# 3_MCU.net
KiCad netlist of a schematic drawn in Altium Designer
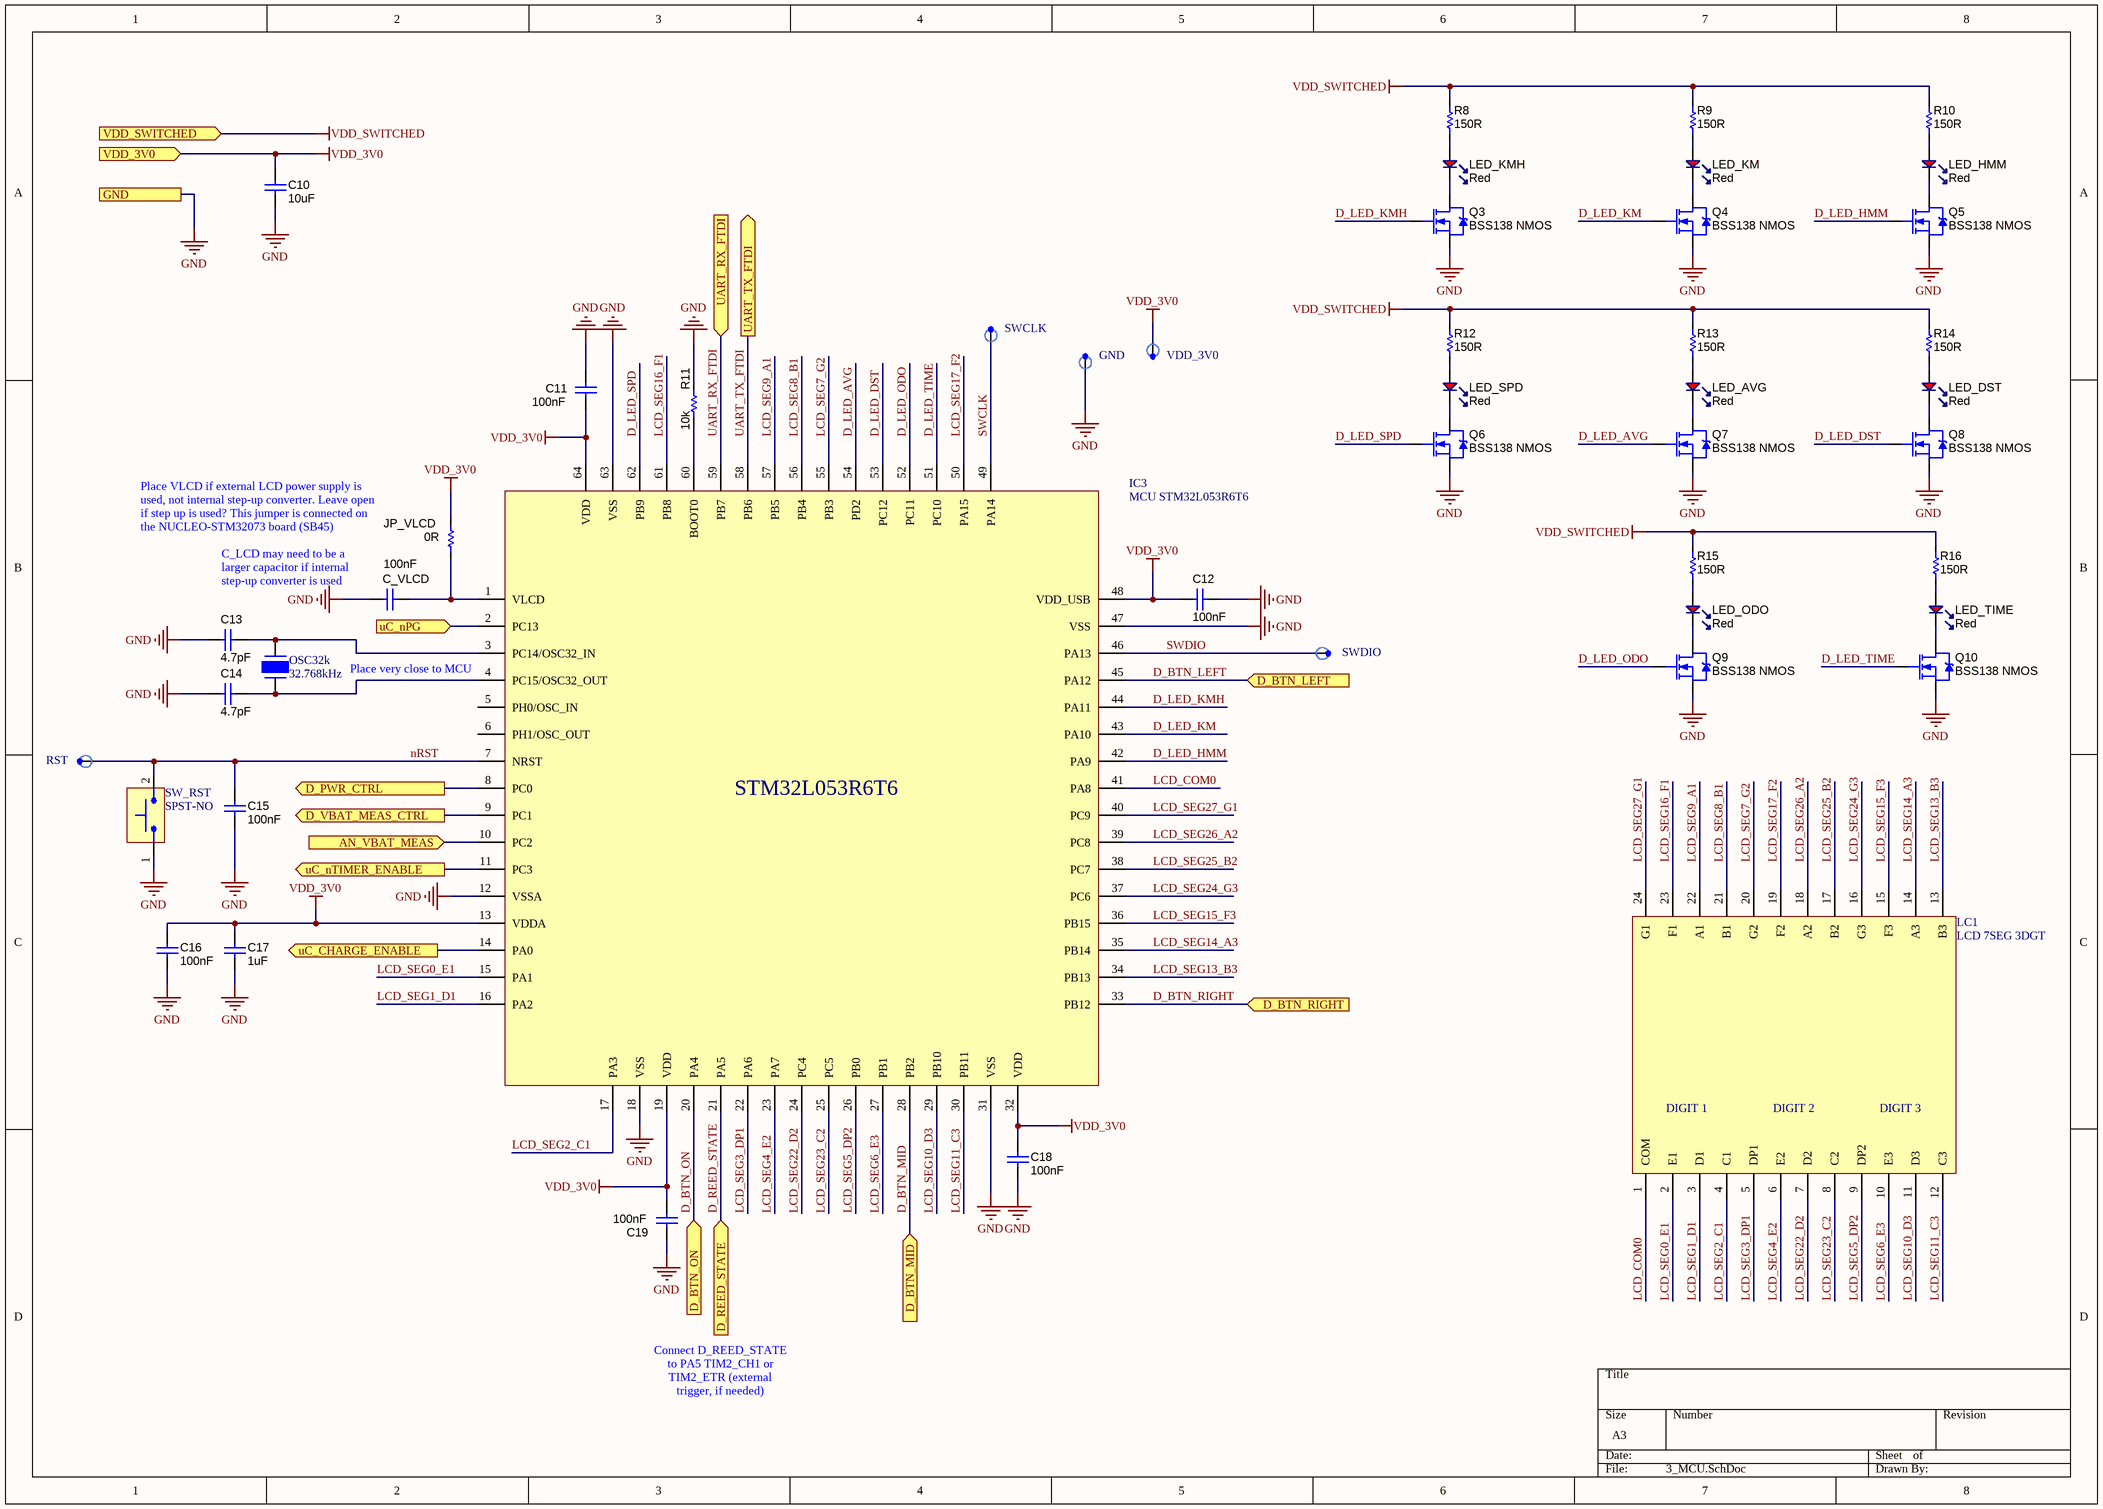
[diagram p0: 3_MCU.SchDoc]

(export (version "E")
  (design (tool "Eeschema 10.0.6"))
  (components
    (comp (ref "C10")
      (value "10uF")
      (footprint "CAP_0603")
      (description "Cermacic Capacitor 0603 16V 10uF")
      (fields (field (name "MANUFACTURER") "n/a"))
      (libsource (lib "Diplomski") (part "CAP_10uF_16V_0603"))
    )
    (comp (ref "C11")
      (value "100nF")
      (footprint "CAP_0603")
      (description "Cermacic Capacitor 0603 50V 100nF")
      (fields (field (name "MANUFACTURER") "n/a"))
      (libsource (lib "Diplomski") (part "CAP_100nF_50V_0603"))
    )
    (comp (ref "C12")
      (value "100nF")
      (footprint "CAP_0603")
      (description "Cermacic Capacitor 0603 50V 100nF")
      (fields (field (name "MANUFACTURER") "n/a"))
      (libsource (lib "Diplomski") (part "CAP_100nF_50V_0603"))
    )
    (comp (ref "C13")
      (value "4.7pF")
      (footprint "CAP_0603")
      (description "Ceramic Capacitor 0603 63V 4.7pF NPO")
      (fields (field (name "MANUFACTURER") "n/a"))
      (libsource (lib "Diplomski") (part "CAP_4.7pF_63V_NPO_0603"))
    )
    (comp (ref "C14")
      (value "4.7pF")
      (footprint "CAP_0603")
      (description "Ceramic Capacitor 0603 63V 4.7pF NPO")
      (fields (field (name "MANUFACTURER") "n/a"))
      (libsource (lib "Diplomski") (part "CAP_4.7pF_63V_NPO_0603"))
    )
    (comp (ref "C15")
      (value "100nF")
      (footprint "CAP_0603")
      (description "Cermacic Capacitor 0603 50V 100nF")
      (fields (field (name "MANUFACTURER") "n/a"))
      (libsource (lib "Diplomski") (part "CAP_100nF_50V_0603"))
    )
    (comp (ref "C16")
      (value "100nF")
      (footprint "CAP_0603")
      (description "Cermacic Capacitor 0603 50V 100nF")
      (fields (field (name "MANUFACTURER") "n/a"))
      (libsource (lib "Diplomski") (part "CAP_100nF_50V_0603"))
    )
    (comp (ref "C17")
      (value "1uF")
      (footprint "CAP_0603")
      (description "Cermacic Capacitor 0603 16V 1uF")
      (fields (field (name "MANUFACTURER") "n/a"))
      (libsource (lib "Diplomski") (part "CAP_1uF_16V_0603"))
    )
    (comp (ref "C18")
      (value "100nF")
      (footprint "CAP_0603")
      (description "Cermacic Capacitor 0603 50V 100nF")
      (fields (field (name "MANUFACTURER") "n/a"))
      (libsource (lib "Diplomski") (part "CAP_100nF_50V_0603"))
    )
    (comp (ref "C19")
      (value "100nF")
      (footprint "CAP_0603")
      (description "Cermacic Capacitor 0603 50V 100nF")
      (fields (field (name "MANUFACTURER") "n/a"))
      (libsource (lib "Diplomski") (part "CAP_100nF_50V_0603"))
    )
    (comp (ref "C_VLCD")
      (value "100nF")
      (footprint "CAP_0603")
      (description "Cermacic Capacitor 0603 50V 100nF")
      (fields (field (name "MANUFACTURER") "n/a"))
      (libsource (lib "Diplomski") (part "CAP_100nF_50V_0603"))
    )
    (comp (ref "GND")
      (value "Testpoint_SMD")
      (footprint "Testpoint_SMD")
      (libsource (lib "Diplomski") (part "Testpoint_SMD"))
    )
    (comp (ref "IC3")
      (value "MCU STM32L053R6T6")
      (footprint "LQFP-64")
      (description "IC MCU STM32L053R6T6 LQFP-64")
      (fields
        (field (name "MANUFACTURER") "STMicroelectronics")
        (field (name "MANUFACTURER PART NUMBER") "STM32L053R6T6")
      )
      (libsource (lib "Diplomski") (part "IC_MCU_STM32L053R6T6_64LQFP"))
    )
    (comp (ref "JP_VLCD")
      (value "0R")
      (footprint "RES_0603")
      (description "Resistor SMD 0603 0R 0.1W 1%")
      (fields (field (name "MANUFACTURER") "n/a") (field (name "TOLERANCE") "1%"))
      (libsource (lib "Diplomski") (part "RES_0R_1%_0.1W_0603"))
    )
    (comp (ref "LC1")
      (value "LCD 7SEG 3DGT")
      (footprint "24 pin 3 digit LCD (7.9mm character height)")
      (description "7 segment LCD display, 3 digits, 0.31in (7.9mm) character height. 3-5V")
      (fields
        (field (name "MANUFACTURER") "Lumex Opto/Components Inc.")
        (field (name "MANUFACTURER PART NUMBER") "LCD-S301C31TR")
      )
      (libsource (lib "Diplomski") (part "LCD_7SEG_3DIGIT_0.31in"))
    )
    (comp (ref "LED_AVG")
      (value "Red")
      (footprint "LED_0603")
      (description "LED Diode SMD Green")
      (fields (field (name "MANUFACTURER") "n/a"))
      (libsource (lib "Diplomski") (part "LED_Red_2V_20mA_0603"))
    )
    (comp (ref "LED_DST")
      (value "Red")
      (footprint "LED_0603")
      (description "LED Diode SMD Green")
      (fields (field (name "MANUFACTURER") "n/a"))
      (libsource (lib "Diplomski") (part "LED_Red_2V_20mA_0603"))
    )
    (comp (ref "LED_HMM")
      (value "Red")
      (footprint "LED_0603")
      (description "LED Diode SMD Green")
      (fields (field (name "MANUFACTURER") "n/a"))
      (libsource (lib "Diplomski") (part "LED_Red_2V_20mA_0603"))
    )
    (comp (ref "LED_KM")
      (value "Red")
      (footprint "LED_0603")
      (description "LED Diode SMD Green")
      (fields (field (name "MANUFACTURER") "n/a"))
      (libsource (lib "Diplomski") (part "LED_Red_2V_20mA_0603"))
    )
    (comp (ref "LED_KMH")
      (value "Red")
      (footprint "LED_0603")
      (description "LED Diode SMD Green")
      (fields (field (name "MANUFACTURER") "n/a"))
      (libsource (lib "Diplomski") (part "LED_Red_2V_20mA_0603"))
    )
    (comp (ref "LED_ODO")
      (value "Red")
      (footprint "LED_0603")
      (description "LED Diode SMD Green")
      (fields (field (name "MANUFACTURER") "n/a"))
      (libsource (lib "Diplomski") (part "LED_Red_2V_20mA_0603"))
    )
    (comp (ref "LED_SPD")
      (value "Red")
      (footprint "LED_0603")
      (description "LED Diode SMD Green")
      (fields (field (name "MANUFACTURER") "n/a"))
      (libsource (lib "Diplomski") (part "LED_Red_2V_20mA_0603"))
    )
    (comp (ref "LED_TIME")
      (value "Red")
      (footprint "LED_0603")
      (description "LED Diode SMD Green")
      (fields (field (name "MANUFACTURER") "n/a"))
      (libsource (lib "Diplomski") (part "LED_Red_2V_20mA_0603"))
    )
    (comp (ref "OSC32k")
      (value "32.768kHz")
      (footprint "2x6mm cylindrical can - 0.7mm through hole")
      (description "SMD Tactile switch 2 pin 6x3.5mm SPST-NO 5mm height")
      (fields (field (name "MANUFACTURER") "YIC") (field (name "MANUFACTURER PART NUMBER") "32.768K26/DT26"))
      (libsource (lib "Diplomski") (part "OSCILLATOR_CRYSTAL_32.768kHz_DT26"))
    )
    (comp (ref "Q3")
      (value "BSS138 NMOS")
      (footprint "SOT-23-3")
      (description "MOSFET N-channel SMD BSS138 220mA 50V")
      (fields (field (name "MANUFACTURER") "ONsemi") (field (name "MANUFACTURER PART NUMBER") "BSS138"))
      (libsource (lib "Diplomski") (part "MOSFET_N_60V_220mA_BSS138_SOT-23"))
    )
    (comp (ref "Q4")
      (value "BSS138 NMOS")
      (footprint "SOT-23-3")
      (description "MOSFET N-channel SMD BSS138 220mA 50V")
      (fields (field (name "MANUFACTURER") "ONsemi") (field (name "MANUFACTURER PART NUMBER") "BSS138"))
      (libsource (lib "Diplomski") (part "MOSFET_N_60V_220mA_BSS138_SOT-23"))
    )
    (comp (ref "Q5")
      (value "BSS138 NMOS")
      (footprint "SOT-23-3")
      (description "MOSFET N-channel SMD BSS138 220mA 50V")
      (fields (field (name "MANUFACTURER") "ONsemi") (field (name "MANUFACTURER PART NUMBER") "BSS138"))
      (libsource (lib "Diplomski") (part "MOSFET_N_60V_220mA_BSS138_SOT-23"))
    )
    (comp (ref "Q6")
      (value "BSS138 NMOS")
      (footprint "SOT-23-3")
      (description "MOSFET N-channel SMD BSS138 220mA 50V")
      (fields (field (name "MANUFACTURER") "ONsemi") (field (name "MANUFACTURER PART NUMBER") "BSS138"))
      (libsource (lib "Diplomski") (part "MOSFET_N_60V_220mA_BSS138_SOT-23"))
    )
    (comp (ref "Q7")
      (value "BSS138 NMOS")
      (footprint "SOT-23-3")
      (description "MOSFET N-channel SMD BSS138 220mA 50V")
      (fields (field (name "MANUFACTURER") "ONsemi") (field (name "MANUFACTURER PART NUMBER") "BSS138"))
      (libsource (lib "Diplomski") (part "MOSFET_N_60V_220mA_BSS138_SOT-23"))
    )
    (comp (ref "Q8")
      (value "BSS138 NMOS")
      (footprint "SOT-23-3")
      (description "MOSFET N-channel SMD BSS138 220mA 50V")
      (fields (field (name "MANUFACTURER") "ONsemi") (field (name "MANUFACTURER PART NUMBER") "BSS138"))
      (libsource (lib "Diplomski") (part "MOSFET_N_60V_220mA_BSS138_SOT-23"))
    )
    (comp (ref "Q9")
      (value "BSS138 NMOS")
      (footprint "SOT-23-3")
      (description "MOSFET N-channel SMD BSS138 220mA 50V")
      (fields (field (name "MANUFACTURER") "ONsemi") (field (name "MANUFACTURER PART NUMBER") "BSS138"))
      (libsource (lib "Diplomski") (part "MOSFET_N_60V_220mA_BSS138_SOT-23"))
    )
    (comp (ref "Q10")
      (value "BSS138 NMOS")
      (footprint "SOT-23-3")
      (description "MOSFET N-channel SMD BSS138 220mA 50V")
      (fields (field (name "MANUFACTURER") "ONsemi") (field (name "MANUFACTURER PART NUMBER") "BSS138"))
      (libsource (lib "Diplomski") (part "MOSFET_N_60V_220mA_BSS138_SOT-23"))
    )
    (comp (ref "R8")
      (value "150R")
      (footprint "RES_0603")
      (description "Resistor SMD 0603 100k 0.1W 1%")
      (fields (field (name "MANUFACTURER") "n/a") (field (name "TOLERANCE") "1%"))
      (libsource (lib "Diplomski") (part "RES_150R_1%_0.1W_0603"))
    )
    (comp (ref "R9")
      (value "150R")
      (footprint "RES_0603")
      (description "Resistor SMD 0603 100k 0.1W 1%")
      (fields (field (name "MANUFACTURER") "n/a") (field (name "TOLERANCE") "1%"))
      (libsource (lib "Diplomski") (part "RES_150R_1%_0.1W_0603"))
    )
    (comp (ref "R10")
      (value "150R")
      (footprint "RES_0603")
      (description "Resistor SMD 0603 100k 0.1W 1%")
      (fields (field (name "MANUFACTURER") "n/a") (field (name "TOLERANCE") "1%"))
      (libsource (lib "Diplomski") (part "RES_150R_1%_0.1W_0603"))
    )
    (comp (ref "R11")
      (value "10k")
      (footprint "RES_0603")
      (description "Resistor SMD 0603 10k 0.1W 1%")
      (fields (field (name "MANUFACTURER") "n/a") (field (name "TOLERANCE") "1%"))
      (libsource (lib "Diplomski") (part "RES_10k_1%_0.1W_0603"))
    )
    (comp (ref "R12")
      (value "150R")
      (footprint "RES_0603")
      (description "Resistor SMD 0603 100k 0.1W 1%")
      (fields (field (name "MANUFACTURER") "n/a") (field (name "TOLERANCE") "1%"))
      (libsource (lib "Diplomski") (part "RES_150R_1%_0.1W_0603"))
    )
    (comp (ref "R13")
      (value "150R")
      (footprint "RES_0603")
      (description "Resistor SMD 0603 100k 0.1W 1%")
      (fields (field (name "MANUFACTURER") "n/a") (field (name "TOLERANCE") "1%"))
      (libsource (lib "Diplomski") (part "RES_150R_1%_0.1W_0603"))
    )
    (comp (ref "R14")
      (value "150R")
      (footprint "RES_0603")
      (description "Resistor SMD 0603 100k 0.1W 1%")
      (fields (field (name "MANUFACTURER") "n/a") (field (name "TOLERANCE") "1%"))
      (libsource (lib "Diplomski") (part "RES_150R_1%_0.1W_0603"))
    )
    (comp (ref "R15")
      (value "150R")
      (footprint "RES_0603")
      (description "Resistor SMD 0603 100k 0.1W 1%")
      (fields (field (name "MANUFACTURER") "n/a") (field (name "TOLERANCE") "1%"))
      (libsource (lib "Diplomski") (part "RES_150R_1%_0.1W_0603"))
    )
    (comp (ref "R16")
      (value "150R")
      (footprint "RES_0603")
      (description "Resistor SMD 0603 100k 0.1W 1%")
      (fields (field (name "MANUFACTURER") "n/a") (field (name "TOLERANCE") "1%"))
      (libsource (lib "Diplomski") (part "RES_150R_1%_0.1W_0603"))
    )
    (comp (ref "RST")
      (value "Testpoint_SMD")
      (footprint "Testpoint_SMD")
      (libsource (lib "Diplomski") (part "Testpoint_SMD"))
    )
    (comp (ref "SWCLK")
      (value "Testpoint_SMD")
      (footprint "Testpoint_SMD")
      (libsource (lib "Diplomski") (part "Testpoint_SMD"))
    )
    (comp (ref "SWDIO")
      (value "Testpoint_SMD")
      (footprint "Testpoint_SMD")
      (libsource (lib "Diplomski") (part "Testpoint_SMD"))
    )
    (comp (ref "SW_RST")
      (value "SPST-NO")
      (footprint "SWITCH_TACTILE_SMD_6X3.5mm_2pin")
      (description "SMD Tactile switch 2 pin 6x3.5mm SPST-NO 5mm height")
      (fields (field (name "MANUFACTURER") "Diptronics") (field (name "MANUFACTURER PART NUMBER") "DTSM-32N"))
      (libsource (lib "Diplomski") (part "SWITCH_SMD_6X3.5mm_2pin"))
    )
    (comp (ref "VDD_3V0")
      (value "Testpoint_SMD")
      (footprint "Testpoint_SMD")
      (libsource (lib "Diplomski") (part "Testpoint_SMD"))
    )
  )
  (nets
    (net (code "1") (name "/AN_VBAT_MEAS") (class "Default")
      (node (ref "IC3") (pin "10") (pinfunction "PC2_10") (pintype "passive"))
    )
    (net (code "2") (name "/D_BTN_LEFT") (class "Default")
      (node (ref "IC3") (pin "45") (pinfunction "PA12_45") (pintype "passive"))
    )
    (net (code "3") (name "/D_BTN_MID") (class "Default")
      (node (ref "IC3") (pin "28") (pinfunction "PB2_28") (pintype "passive"))
    )
    (net (code "4") (name "/D_BTN_ON") (class "Default")
      (node (ref "IC3") (pin "20") (pinfunction "PA4_20") (pintype "passive"))
    )
    (net (code "5") (name "/D_BTN_RIGHT") (class "Default")
      (node (ref "IC3") (pin "33") (pinfunction "PB12_33") (pintype "passive"))
    )
    (net (code "6") (name "/D_LED_AVG") (class "Default")
      (node (ref "IC3") (pin "54") (pinfunction "PD2_54") (pintype "passive"))
      (node (ref "Q7") (pin "1") (pinfunction "G_1") (pintype "passive"))
    )
    (net (code "7") (name "/D_LED_DST") (class "Default")
      (node (ref "IC3") (pin "53") (pinfunction "PC12_53") (pintype "passive"))
      (node (ref "Q8") (pin "1") (pinfunction "G_1") (pintype "passive"))
    )
    (net (code "8") (name "/D_LED_HMM") (class "Default")
      (node (ref "IC3") (pin "42") (pinfunction "PA9_42") (pintype "passive"))
      (node (ref "Q5") (pin "1") (pinfunction "G_1") (pintype "passive"))
    )
    (net (code "9") (name "/D_LED_KM") (class "Default")
      (node (ref "IC3") (pin "43") (pinfunction "PA10_43") (pintype "passive"))
      (node (ref "Q4") (pin "1") (pinfunction "G_1") (pintype "passive"))
    )
    (net (code "10") (name "/D_LED_KMH") (class "Default")
      (node (ref "IC3") (pin "44") (pinfunction "PA11_44") (pintype "passive"))
      (node (ref "Q3") (pin "1") (pinfunction "G_1") (pintype "passive"))
    )
    (net (code "11") (name "/D_LED_ODO") (class "Default")
      (node (ref "IC3") (pin "52") (pinfunction "PC11_52") (pintype "passive"))
      (node (ref "Q9") (pin "1") (pinfunction "G_1") (pintype "passive"))
    )
    (net (code "12") (name "/D_LED_SPD") (class "Default")
      (node (ref "IC3") (pin "62") (pinfunction "PB9_62") (pintype "passive"))
      (node (ref "Q6") (pin "1") (pinfunction "G_1") (pintype "passive"))
    )
    (net (code "13") (name "/D_LED_TIME") (class "Default")
      (node (ref "IC3") (pin "51") (pinfunction "PC10_51") (pintype "passive"))
      (node (ref "Q10") (pin "1") (pinfunction "G_1") (pintype "passive"))
    )
    (net (code "14") (name "/D_PWR_CTRL") (class "Default")
      (node (ref "IC3") (pin "8") (pinfunction "PC0_8") (pintype "passive"))
    )
    (net (code "15") (name "/D_REED_STATE") (class "Default")
      (node (ref "IC3") (pin "21") (pinfunction "PA5_21") (pintype "passive"))
    )
    (net (code "16") (name "/D_VBAT_MEAS_CTRL") (class "Default")
      (node (ref "IC3") (pin "9") (pinfunction "PC1_9") (pintype "passive"))
    )
    (net (code "17") (name "/LCD_COM0") (class "Default")
      (node (ref "IC3") (pin "41") (pinfunction "PA8_41") (pintype "passive"))
      (node (ref "LC1") (pin "1") (pinfunction "COM_1") (pintype "passive"))
    )
    (net (code "18") (name "/LCD_SEG0_E1") (class "Default")
      (node (ref "IC3") (pin "15") (pinfunction "PA1_15") (pintype "passive"))
      (node (ref "LC1") (pin "2") (pinfunction "E1_2") (pintype "passive"))
    )
    (net (code "19") (name "/LCD_SEG1_D1") (class "Default")
      (node (ref "IC3") (pin "16") (pinfunction "PA2_16") (pintype "passive"))
      (node (ref "LC1") (pin "3") (pinfunction "D1_3") (pintype "passive"))
    )
    (net (code "20") (name "/LCD_SEG2_C1") (class "Default")
      (node (ref "IC3") (pin "17") (pinfunction "PA3_17") (pintype "passive"))
      (node (ref "LC1") (pin "4") (pinfunction "C1_4") (pintype "passive"))
    )
    (net (code "21") (name "/LCD_SEG3_DP1") (class "Default")
      (node (ref "IC3") (pin "22") (pinfunction "PA6_22") (pintype "passive"))
      (node (ref "LC1") (pin "5") (pinfunction "DP1_5") (pintype "passive"))
    )
    (net (code "22") (name "/LCD_SEG4_E2") (class "Default")
      (node (ref "IC3") (pin "23") (pinfunction "PA7_23") (pintype "passive"))
      (node (ref "LC1") (pin "6") (pinfunction "E2_6") (pintype "passive"))
    )
    (net (code "23") (name "/LCD_SEG5_DP2") (class "Default")
      (node (ref "IC3") (pin "26") (pinfunction "PB0_26") (pintype "passive"))
      (node (ref "LC1") (pin "9") (pinfunction "DP2_9") (pintype "passive"))
    )
    (net (code "24") (name "/LCD_SEG6_E3") (class "Default")
      (node (ref "IC3") (pin "27") (pinfunction "PB1_27") (pintype "passive"))
      (node (ref "LC1") (pin "10") (pinfunction "E3_10") (pintype "passive"))
    )
    (net (code "25") (name "/LCD_SEG7_G2") (class "Default")
      (node (ref "IC3") (pin "55") (pinfunction "PB3_55") (pintype "passive"))
      (node (ref "LC1") (pin "20") (pinfunction "G2_20") (pintype "passive"))
    )
    (net (code "26") (name "/LCD_SEG8_B1") (class "Default")
      (node (ref "IC3") (pin "56") (pinfunction "PB4_56") (pintype "passive"))
      (node (ref "LC1") (pin "21") (pinfunction "B1_21") (pintype "passive"))
    )
    (net (code "27") (name "/LCD_SEG9_A1") (class "Default")
      (node (ref "IC3") (pin "57") (pinfunction "PB5_57") (pintype "passive"))
      (node (ref "LC1") (pin "22") (pinfunction "A1_22") (pintype "passive"))
    )
    (net (code "28") (name "/LCD_SEG10_D3") (class "Default")
      (node (ref "IC3") (pin "29") (pinfunction "PB10_29") (pintype "passive"))
      (node (ref "LC1") (pin "11") (pinfunction "D3_11") (pintype "passive"))
    )
    (net (code "29") (name "/LCD_SEG11_C3") (class "Default")
      (node (ref "IC3") (pin "30") (pinfunction "PB11_30") (pintype "passive"))
      (node (ref "LC1") (pin "12") (pinfunction "C3_12") (pintype "passive"))
    )
    (net (code "30") (name "/LCD_SEG13_B3") (class "Default")
      (node (ref "IC3") (pin "34") (pinfunction "PB13_34") (pintype "passive"))
      (node (ref "LC1") (pin "13") (pinfunction "B3_13") (pintype "passive"))
    )
    (net (code "31") (name "/LCD_SEG14_A3") (class "Default")
      (node (ref "IC3") (pin "35") (pinfunction "PB14_35") (pintype "passive"))
      (node (ref "LC1") (pin "14") (pinfunction "A3_14") (pintype "passive"))
    )
    (net (code "32") (name "/LCD_SEG15_F3") (class "Default")
      (node (ref "IC3") (pin "36") (pinfunction "PB15_36") (pintype "passive"))
      (node (ref "LC1") (pin "15") (pinfunction "F3_15") (pintype "passive"))
    )
    (net (code "33") (name "/LCD_SEG16_F1") (class "Default")
      (node (ref "IC3") (pin "61") (pinfunction "PB8_61") (pintype "passive"))
      (node (ref "LC1") (pin "23") (pinfunction "F1_23") (pintype "passive"))
    )
    (net (code "34") (name "/LCD_SEG17_F2") (class "Default")
      (node (ref "IC3") (pin "50") (pinfunction "PA15_50") (pintype "passive"))
      (node (ref "LC1") (pin "19") (pinfunction "F2_19") (pintype "passive"))
    )
    (net (code "35") (name "/LCD_SEG22_D2") (class "Default")
      (node (ref "IC3") (pin "24") (pinfunction "PC4_24") (pintype "passive"))
      (node (ref "LC1") (pin "7") (pinfunction "D2_7") (pintype "passive"))
    )
    (net (code "36") (name "/LCD_SEG23_C2") (class "Default")
      (node (ref "IC3") (pin "25") (pinfunction "PC5_25") (pintype "passive"))
      (node (ref "LC1") (pin "8") (pinfunction "C2_8") (pintype "passive"))
    )
    (net (code "37") (name "/LCD_SEG24_G3") (class "Default")
      (node (ref "IC3") (pin "37") (pinfunction "PC6_37") (pintype "passive"))
      (node (ref "LC1") (pin "16") (pinfunction "G3_16") (pintype "passive"))
    )
    (net (code "38") (name "/LCD_SEG25_B2") (class "Default")
      (node (ref "IC3") (pin "38") (pinfunction "PC7_38") (pintype "passive"))
      (node (ref "LC1") (pin "17") (pinfunction "B2_17") (pintype "passive"))
    )
    (net (code "39") (name "/LCD_SEG26_A2") (class "Default")
      (node (ref "IC3") (pin "39") (pinfunction "PC8_39") (pintype "passive"))
      (node (ref "LC1") (pin "18") (pinfunction "A2_18") (pintype "passive"))
    )
    (net (code "40") (name "/LCD_SEG27_G1") (class "Default")
      (node (ref "IC3") (pin "40") (pinfunction "PC9_40") (pintype "passive"))
      (node (ref "LC1") (pin "24") (pinfunction "G1_24") (pintype "passive"))
    )
    (net (code "41") (name "/SWCLK") (class "Default")
      (node (ref "IC3") (pin "49") (pinfunction "PA14_49") (pintype "passive"))
      (node (ref "SWCLK") (pin "1") (pinfunction "1_1") (pintype "passive"))
    )
    (net (code "42") (name "/SWDIO") (class "Default")
      (node (ref "IC3") (pin "46") (pinfunction "PA13_46") (pintype "passive"))
      (node (ref "SWDIO") (pin "1") (pinfunction "1_1") (pintype "passive"))
    )
    (net (code "43") (name "/UART_RX_FTDI") (class "Default")
      (node (ref "IC3") (pin "59") (pinfunction "PB7_59") (pintype "passive"))
    )
    (net (code "44") (name "/UART_TX_FTDI") (class "Default")
      (node (ref "IC3") (pin "58") (pinfunction "PB6_58") (pintype "passive"))
    )
    (net (code "45") (name "/nRST") (class "Default")
      (node (ref "C15") (pin "1") (pinfunction "1_1") (pintype "passive"))
      (node (ref "IC3") (pin "7") (pinfunction "NRST_7") (pintype "passive"))
      (node (ref "RST") (pin "1") (pinfunction "1_1") (pintype "passive"))
      (node (ref "SW_RST") (pin "2") (pinfunction "2_2") (pintype "passive"))
    )
    (net (code "46") (name "/uC_CHARGE_ENABLE") (class "Default")
      (node (ref "IC3") (pin "14") (pinfunction "PA0_14") (pintype "passive"))
    )
    (net (code "47") (name "/uC_nPG") (class "Default")
      (node (ref "IC3") (pin "2") (pinfunction "PC13_2") (pintype "passive"))
    )
    (net (code "48") (name "/uC_nTIMER_ENABLE") (class "Default")
      (node (ref "IC3") (pin "11") (pinfunction "PC3_11") (pintype "passive"))
    )
    (net (code "49") (name "GND") (class "Default")
      (node (ref "C10") (pin "2") (pinfunction "2_2") (pintype "passive"))
      (node (ref "C11") (pin "2") (pinfunction "2_2") (pintype "passive"))
      (node (ref "C12") (pin "2") (pinfunction "2_2") (pintype "passive"))
      (node (ref "C13") (pin "2") (pinfunction "2_2") (pintype "passive"))
      (node (ref "C14") (pin "2") (pinfunction "2_2") (pintype "passive"))
      (node (ref "C15") (pin "2") (pinfunction "2_2") (pintype "passive"))
      (node (ref "C16") (pin "2") (pinfunction "2_2") (pintype "passive"))
      (node (ref "C17") (pin "2") (pinfunction "2_2") (pintype "passive"))
      (node (ref "C18") (pin "2") (pinfunction "2_2") (pintype "passive"))
      (node (ref "C19") (pin "1") (pinfunction "1_1") (pintype "passive"))
      (node (ref "C_VLCD") (pin "2") (pinfunction "2_2") (pintype "passive"))
      (node (ref "GND") (pin "1") (pinfunction "1_1") (pintype "passive"))
      (node (ref "IC3") (pin "12") (pinfunction "VSSA_12") (pintype "passive"))
      (node (ref "IC3") (pin "18") (pinfunction "VSS_18") (pintype "passive"))
      (node (ref "IC3") (pin "31") (pinfunction "VSS_31") (pintype "passive"))
      (node (ref "IC3") (pin "47") (pinfunction "VSS_47") (pintype "passive"))
      (node (ref "IC3") (pin "63") (pinfunction "VSS_63") (pintype "passive"))
      (node (ref "Q10") (pin "2") (pinfunction "S_2") (pintype "passive"))
      (node (ref "Q3") (pin "2") (pinfunction "S_2") (pintype "passive"))
      (node (ref "Q4") (pin "2") (pinfunction "S_2") (pintype "passive"))
      (node (ref "Q5") (pin "2") (pinfunction "S_2") (pintype "passive"))
      (node (ref "Q6") (pin "2") (pinfunction "S_2") (pintype "passive"))
      (node (ref "Q7") (pin "2") (pinfunction "S_2") (pintype "passive"))
      (node (ref "Q8") (pin "2") (pinfunction "S_2") (pintype "passive"))
      (node (ref "Q9") (pin "2") (pinfunction "S_2") (pintype "passive"))
      (node (ref "R11") (pin "2") (pinfunction "2_2") (pintype "passive"))
      (node (ref "SW_RST") (pin "1") (pinfunction "1_1") (pintype "passive"))
    )
    (net (code "50") (name "Net-(IC3-BOOT0)") (class "Default")
      (node (ref "IC3") (pin "60") (pinfunction "BOOT0_60") (pintype "passive"))
      (node (ref "R11") (pin "1") (pinfunction "1_1") (pintype "passive"))
    )
    (net (code "51") (name "Net-(IC3-PC14{slash}OSC32_IN)") (class "Default")
      (node (ref "C13") (pin "1") (pinfunction "1_1") (pintype "passive"))
      (node (ref "IC3") (pin "3") (pinfunction "PC14/OSC32_IN_3") (pintype "passive"))
      (node (ref "OSC32k") (pin "1") (pinfunction "1_1") (pintype "passive"))
    )
    (net (code "52") (name "Net-(IC3-PC15{slash}OSC32_OUT)") (class "Default")
      (node (ref "C14") (pin "1") (pinfunction "1_1") (pintype "passive"))
      (node (ref "IC3") (pin "4") (pinfunction "PC15/OSC32_OUT_4") (pintype "passive"))
      (node (ref "OSC32k") (pin "2") (pinfunction "2_2") (pintype "passive"))
    )
    (net (code "53") (name "Net-(IC3-VLCD)") (class "Default")
      (node (ref "C_VLCD") (pin "1") (pinfunction "1_1") (pintype "passive"))
      (node (ref "IC3") (pin "1") (pinfunction "VLCD_1") (pintype "passive"))
      (node (ref "JP_VLCD") (pin "1") (pinfunction "1_1") (pintype "passive"))
    )
    (net (code "54") (name "Net-(LED_AVG-PadA)") (class "Default")
      (node (ref "LED_AVG") (pin "A") (pinfunction "A_A") (pintype "passive"))
      (node (ref "R13") (pin "1") (pinfunction "1_1") (pintype "passive"))
    )
    (net (code "55") (name "Net-(LED_DST-PadA)") (class "Default")
      (node (ref "LED_DST") (pin "A") (pinfunction "A_A") (pintype "passive"))
      (node (ref "R14") (pin "1") (pinfunction "1_1") (pintype "passive"))
    )
    (net (code "56") (name "Net-(LED_HMM-PadA)") (class "Default")
      (node (ref "LED_HMM") (pin "A") (pinfunction "A_A") (pintype "passive"))
      (node (ref "R10") (pin "1") (pinfunction "1_1") (pintype "passive"))
    )
    (net (code "57") (name "Net-(LED_KM-PadA)") (class "Default")
      (node (ref "LED_KM") (pin "A") (pinfunction "A_A") (pintype "passive"))
      (node (ref "R9") (pin "1") (pinfunction "1_1") (pintype "passive"))
    )
    (net (code "58") (name "Net-(LED_KMH-PadA)") (class "Default")
      (node (ref "LED_KMH") (pin "A") (pinfunction "A_A") (pintype "passive"))
      (node (ref "R8") (pin "1") (pinfunction "1_1") (pintype "passive"))
    )
    (net (code "59") (name "Net-(LED_ODO-PadA)") (class "Default")
      (node (ref "LED_ODO") (pin "A") (pinfunction "A_A") (pintype "passive"))
      (node (ref "R15") (pin "1") (pinfunction "1_1") (pintype "passive"))
    )
    (net (code "60") (name "Net-(LED_SPD-PadA)") (class "Default")
      (node (ref "LED_SPD") (pin "A") (pinfunction "A_A") (pintype "passive"))
      (node (ref "R12") (pin "1") (pinfunction "1_1") (pintype "passive"))
    )
    (net (code "61") (name "Net-(LED_TIME-PadA)") (class "Default")
      (node (ref "LED_TIME") (pin "A") (pinfunction "A_A") (pintype "passive"))
      (node (ref "R16") (pin "1") (pinfunction "1_1") (pintype "passive"))
    )
    (net (code "62") (name "Net-(Q3-D)") (class "Default")
      (node (ref "LED_KMH") (pin "K") (pinfunction "K_K") (pintype "passive"))
      (node (ref "Q3") (pin "3") (pinfunction "D_3") (pintype "passive"))
    )
    (net (code "63") (name "Net-(Q4-D)") (class "Default")
      (node (ref "LED_KM") (pin "K") (pinfunction "K_K") (pintype "passive"))
      (node (ref "Q4") (pin "3") (pinfunction "D_3") (pintype "passive"))
    )
    (net (code "64") (name "Net-(Q5-D)") (class "Default")
      (node (ref "LED_HMM") (pin "K") (pinfunction "K_K") (pintype "passive"))
      (node (ref "Q5") (pin "3") (pinfunction "D_3") (pintype "passive"))
    )
    (net (code "65") (name "Net-(Q6-D)") (class "Default")
      (node (ref "LED_SPD") (pin "K") (pinfunction "K_K") (pintype "passive"))
      (node (ref "Q6") (pin "3") (pinfunction "D_3") (pintype "passive"))
    )
    (net (code "66") (name "Net-(Q7-D)") (class "Default")
      (node (ref "LED_AVG") (pin "K") (pinfunction "K_K") (pintype "passive"))
      (node (ref "Q7") (pin "3") (pinfunction "D_3") (pintype "passive"))
    )
    (net (code "67") (name "Net-(Q8-D)") (class "Default")
      (node (ref "LED_DST") (pin "K") (pinfunction "K_K") (pintype "passive"))
      (node (ref "Q8") (pin "3") (pinfunction "D_3") (pintype "passive"))
    )
    (net (code "68") (name "Net-(Q9-D)") (class "Default")
      (node (ref "LED_ODO") (pin "K") (pinfunction "K_K") (pintype "passive"))
      (node (ref "Q9") (pin "3") (pinfunction "D_3") (pintype "passive"))
    )
    (net (code "69") (name "Net-(Q10-D)") (class "Default")
      (node (ref "LED_TIME") (pin "K") (pinfunction "K_K") (pintype "passive"))
      (node (ref "Q10") (pin "3") (pinfunction "D_3") (pintype "passive"))
    )
    (net (code "70") (name "VDD_3V0") (class "Default")
      (node (ref "C10") (pin "1") (pinfunction "1_1") (pintype "passive"))
      (node (ref "C11") (pin "1") (pinfunction "1_1") (pintype "passive"))
      (node (ref "C12") (pin "1") (pinfunction "1_1") (pintype "passive"))
      (node (ref "C16") (pin "1") (pinfunction "1_1") (pintype "passive"))
      (node (ref "C17") (pin "1") (pinfunction "1_1") (pintype "passive"))
      (node (ref "C18") (pin "1") (pinfunction "1_1") (pintype "passive"))
      (node (ref "C19") (pin "2") (pinfunction "2_2") (pintype "passive"))
      (node (ref "IC3") (pin "13") (pinfunction "VDDA_13") (pintype "passive"))
      (node (ref "IC3") (pin "19") (pinfunction "VDD_19") (pintype "passive"))
      (node (ref "IC3") (pin "32") (pinfunction "VDD_32") (pintype "passive"))
      (node (ref "IC3") (pin "48") (pinfunction "VDD_USB_48") (pintype "passive"))
      (node (ref "IC3") (pin "64") (pinfunction "VDD_64") (pintype "passive"))
      (node (ref "JP_VLCD") (pin "2") (pinfunction "2_2") (pintype "passive"))
      (node (ref "VDD_3V0") (pin "1") (pinfunction "1_1") (pintype "passive"))
    )
    (net (code "71") (name "VDD_SWITCHED") (class "Default")
      (node (ref "R10") (pin "2") (pinfunction "2_2") (pintype "passive"))
      (node (ref "R12") (pin "2") (pinfunction "2_2") (pintype "passive"))
      (node (ref "R13") (pin "2") (pinfunction "2_2") (pintype "passive"))
      (node (ref "R14") (pin "2") (pinfunction "2_2") (pintype "passive"))
      (node (ref "R15") (pin "2") (pinfunction "2_2") (pintype "passive"))
      (node (ref "R16") (pin "2") (pinfunction "2_2") (pintype "passive"))
      (node (ref "R8") (pin "2") (pinfunction "2_2") (pintype "passive"))
      (node (ref "R9") (pin "2") (pinfunction "2_2") (pintype "passive"))
    )
    (net (code "72") (name "unconnected-(IC3-PH0{slash}OSC_IN-Pad5)") (class "Default")
      (node (ref "IC3") (pin "5") (pinfunction "PH0/OSC_IN_5") (pintype "passive"))
    )
    (net (code "73") (name "unconnected-(IC3-PH1{slash}OSC_OUT-Pad6)") (class "Default")
      (node (ref "IC3") (pin "6") (pinfunction "PH1/OSC_OUT_6") (pintype "passive"))
    )
  )
)
